# Ch_trig.net
KiCad netlist of a schematic drawn in Altium Designer
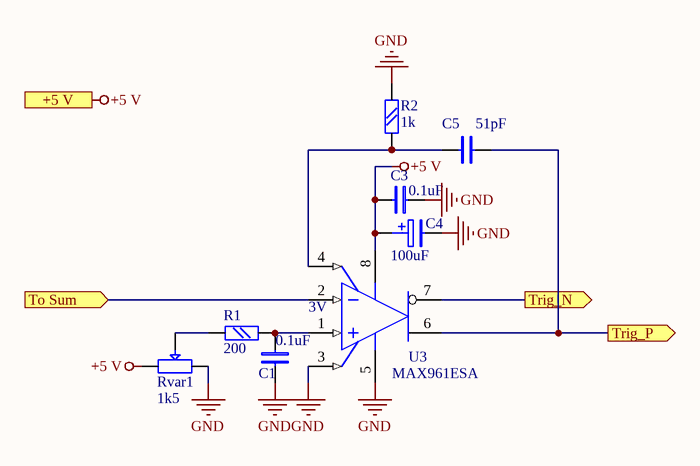
[diagram p0: Ch_trig.SchDoc]

(export (version "E")
  (design (tool "Eeschema 10.0.6"))
  (components
    (comp (ref "C1") (value "0.1uF") (footprint "chip0805") (libsource (lib "vDevice") (part "C")))
    (comp (ref "C3") (value "0.1uF") (footprint "chip0805") (libsource (lib "vDevice") (part "C")))
    (comp (ref "C4") (value "100uF") (footprint "CEL-SMD300") (libsource (lib "vDevice") (part "C POL")))
    (comp (ref "C5") (value "51pF") (footprint "chip0805") (libsource (lib "vDevice") (part "C")))
    (comp (ref "R1") (value "200") (footprint "chip0805") (libsource (lib "vDevice") (part "R")))
    (comp (ref "R2") (value "1k") (footprint "chip0805") (libsource (lib "vDevice") (part "R")))
    (comp (ref "Rvar1") (value "1k5") (footprint "RVAR4") (libsource (lib "vDevice") (part "R VAR")))
    (comp (ref "U3")
      (value "MAX961ESA")
      (footprint "NSO8_N")
      (description "Single Ultra-High-Speed, +3V/+5V, Beyond-the-Rails Comparator")
      (fields (field (name "PUBLISHER") "Altium Limited"))
      (libsource (lib "Maxim Analog Comparator") (part "MAX961ESA"))
    )
  )
  (nets
    (net (code "1") (name "+5 V") (class "Default")
      (node (ref "C3") (pin "2") (pinfunction "2_2") (pintype "passive"))
      (node (ref "C4") (pin "+") (pinfunction "+_+") (pintype "passive"))
      (node (ref "Rvar1") (pin "1") (pinfunction "1_1") (pintype "passive"))
      (node (ref "U3") (pin "8") (pinfunction "V+_8") (pintype "power_in"))
    )
    (net (code "2") (name "/To Sum") (class "Default")
      (node (ref "U3") (pin "2") (pinfunction "IN-_2") (pintype "input"))
    )
    (net (code "3") (name "/Trig_N") (class "Default")
      (node (ref "U3") (pin "7") (pinfunction "~{Q}_7") (pintype "tri_state"))
    )
    (net (code "4") (name "/Trig_P") (class "Default")
      (node (ref "C5") (pin "2") (pinfunction "2_2") (pintype "passive"))
      (node (ref "U3") (pin "6") (pinfunction "Q_6") (pintype "tri_state"))
    )
    (net (code "5") (name "GND") (class "Default")
      (node (ref "C1") (pin "1") (pinfunction "1_1") (pintype "passive"))
      (node (ref "C3") (pin "1") (pinfunction "1_1") (pintype "passive"))
      (node (ref "C4") (pin "-") (pinfunction "-_-") (pintype "passive"))
      (node (ref "R2") (pin "2") (pinfunction "2_2") (pintype "passive"))
      (node (ref "Rvar1") (pin "3") (pinfunction "3_3") (pintype "passive"))
      (node (ref "U3") (pin "3") (pinfunction "SHDN_3") (pintype "input"))
      (node (ref "U3") (pin "5") (pinfunction "GND_5") (pintype "power_in"))
    )
    (net (code "6") (name "Net-(R1-Pad1)") (class "Default")
      (node (ref "R1") (pin "1") (pinfunction "1_1") (pintype "passive"))
      (node (ref "Rvar1") (pin "2") (pinfunction "2_2") (pintype "passive"))
    )
    (net (code "7") (name "Net-(U3-IN+)") (class "Default")
      (node (ref "C1") (pin "2") (pinfunction "2_2") (pintype "passive"))
      (node (ref "R1") (pin "2") (pinfunction "2_2") (pintype "passive"))
      (node (ref "U3") (pin "1") (pinfunction "IN+_1") (pintype "input"))
    )
    (net (code "8") (name "Net-(U3-LE)") (class "Default")
      (node (ref "C5") (pin "1") (pinfunction "1_1") (pintype "passive"))
      (node (ref "R2") (pin "1") (pinfunction "1_1") (pintype "passive"))
      (node (ref "U3") (pin "4") (pinfunction "LE_4") (pintype "input"))
    )
  )
)
